# Transponder_Proaut_V1.net
KiCad netlist of a schematic drawn in EAGLE
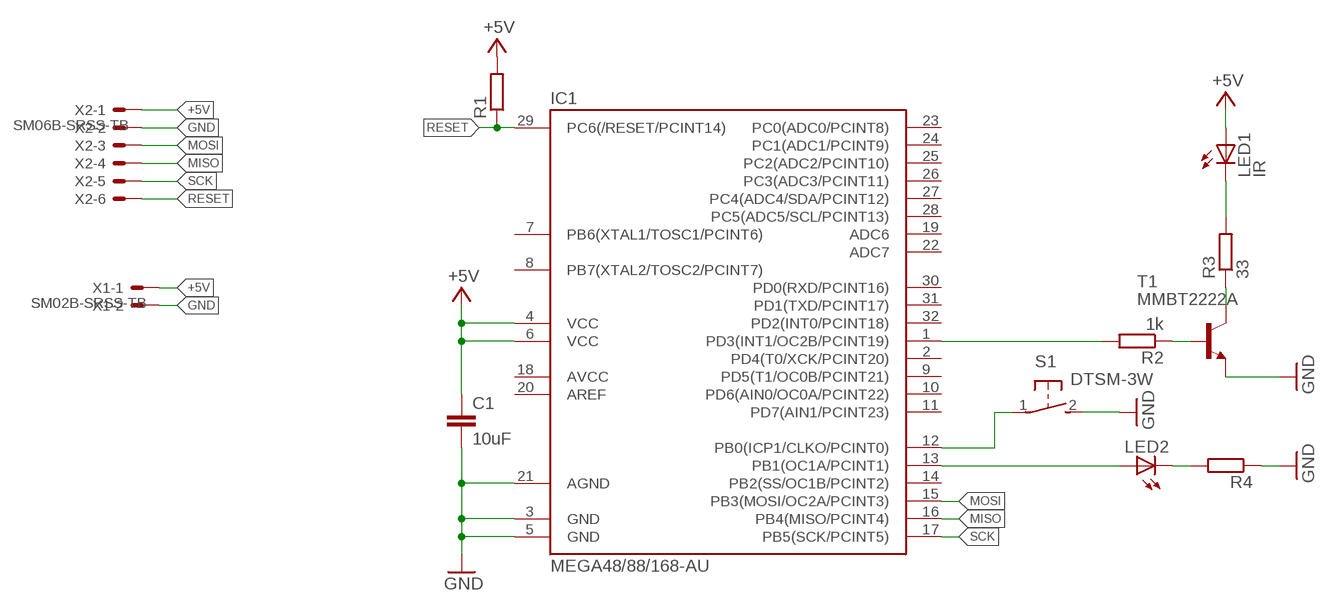
[diagram p0: schematic, sheet 1]

(export (version "E")
  (design (tool "Eeschema 10.0.6"))
  (components
    (comp (ref "C1")
      (value "10uF")
      (footprint "eagle-import:C0805")
      (libsource (lib "eagle-import") (part "C-EUC0805"))
    )
    (comp (ref "IC1")
      (value "MEGA48/88/168-AU")
      (footprint "eagle-import:TQFP32-08")
      (libsource (lib "eagle-import") (part "MEGA48/88/168-AU"))
    )
    (comp (ref "LED1")
      (value "IR")
      (footprint "eagle-import:LED5MM")
      (libsource (lib "eagle-import") (part "LED5MM"))
    )
    (comp (ref "LED2")
      (value "LEDSML1206")
      (footprint "eagle-import:SML1206")
      (libsource (lib "eagle-import") (part "LEDSML1206"))
    )
    (comp (ref "R1")
      (value "R-EU_R0805")
      (footprint "eagle-import:R0805@1")
      (libsource (lib "eagle-import") (part "R-EU_R0805"))
    )
    (comp (ref "R2")
      (value "1k")
      (footprint "eagle-import:R0805@1")
      (libsource (lib "eagle-import") (part "R-EU_R0805"))
    )
    (comp (ref "R3")
      (value "33")
      (footprint "eagle-import:R0805@1")
      (libsource (lib "eagle-import") (part "R-EU_R0805"))
    )
    (comp (ref "R4")
      (value "R-EU_R0805")
      (footprint "eagle-import:R0805@1")
      (libsource (lib "eagle-import") (part "R-EU_R0805"))
    )
    (comp (ref "S1")
      (value "DTSM-3W")
      (footprint "eagle-import:DTSM-3W")
      (libsource (lib "eagle-import") (part "DTSM-3W"))
    )
    (comp (ref "T1")
      (value "MMBT2222A")
      (footprint "eagle-import:SOT23-BEC")
      (libsource (lib "eagle-import") (part "-NPN-SOT23-BECMMBT2222ALT1"))
    )
    (comp (ref "X1")
      (value "SM02B-SRSS-TB")
      (footprint "eagle-import:SM02B-SRSS-TB")
      (libsource (lib "eagle-import") (part "?M02B-SRSS-TBS"))
    )
    (comp (ref "X2")
      (value "SM06B-SRSS-TB")
      (footprint "eagle-import:SM06B-SRSS-TB")
      (libsource (lib "eagle-import") (part "?M06B-SRSS-TBS"))
    )
  )
  (nets
    (net (code "1") (name "+5V") (class "Default")
      (node (ref "C1") (pin "1") (pinfunction "1_1") (pintype "passive"))
      (node (ref "IC1") (pin "4") (pinfunction "VCC_4") (pintype "power_in"))
      (node (ref "IC1") (pin "6") (pinfunction "VCC_6") (pintype "power_in"))
      (node (ref "LED1") (pin "A") (pinfunction "A_A") (pintype "passive"))
      (node (ref "R1") (pin "2") (pinfunction "2_2") (pintype "passive"))
      (node (ref "X1") (pin "1") (pinfunction "S_1") (pintype "passive"))
      (node (ref "X2") (pin "1") (pinfunction "S_1") (pintype "passive"))
    )
    (net (code "2") (name "GND") (class "Default")
      (node (ref "C1") (pin "2") (pinfunction "2_2") (pintype "passive"))
      (node (ref "IC1") (pin "21") (pinfunction "AGND_21") (pintype "power_in"))
      (node (ref "IC1") (pin "3") (pinfunction "GND_3") (pintype "power_in"))
      (node (ref "IC1") (pin "5") (pinfunction "GND_5") (pintype "power_in"))
      (node (ref "R4") (pin "1") (pinfunction "1_1") (pintype "passive"))
      (node (ref "S1") (pin "2") (pinfunction "2_2") (pintype "passive"))
      (node (ref "T1") (pin "E") (pinfunction "E_E") (pintype "passive"))
      (node (ref "X1") (pin "2") (pinfunction "S_2") (pintype "passive"))
      (node (ref "X2") (pin "2") (pinfunction "S_2") (pintype "passive"))
    )
    (net (code "3") (name "MISO") (class "Default")
      (node (ref "IC1") (pin "16") (pinfunction "PB4(MISO/PCINT4)_16") (pintype "bidirectional"))
      (node (ref "X2") (pin "4") (pinfunction "S_4") (pintype "passive"))
    )
    (net (code "4") (name "MOSI") (class "Default")
      (node (ref "IC1") (pin "15") (pinfunction "PB3(MOSI/OC2A/PCINT3)_15") (pintype "bidirectional"))
      (node (ref "X2") (pin "3") (pinfunction "S_3") (pintype "passive"))
    )
    (net (code "5") (name "Net-(IC1-PB0(ICP1{slash}CLKO{slash}PCINT0))") (class "Default")
      (node (ref "IC1") (pin "12") (pinfunction "PB0(ICP1/CLKO/PCINT0)_12") (pintype "bidirectional"))
      (node (ref "S1") (pin "1") (pinfunction "1_1") (pintype "passive"))
    )
    (net (code "6") (name "Net-(IC1-PB1(OC1A{slash}PCINT1))") (class "Default")
      (node (ref "IC1") (pin "13") (pinfunction "PB1(OC1A/PCINT1)_13") (pintype "bidirectional"))
      (node (ref "LED2") (pin "A") (pinfunction "A_A") (pintype "passive"))
    )
    (net (code "7") (name "Net-(IC1-PD3(INT1{slash}OC2B{slash}PCINT19))") (class "Default")
      (node (ref "IC1") (pin "1") (pinfunction "PD3(INT1/OC2B/PCINT19)_1") (pintype "bidirectional"))
      (node (ref "R2") (pin "2") (pinfunction "2_2") (pintype "passive"))
    )
    (net (code "8") (name "Net-(LED1-C)") (class "Default")
      (node (ref "LED1") (pin "K") (pinfunction "C_K") (pintype "passive"))
      (node (ref "R3") (pin "2") (pinfunction "2_2") (pintype "passive"))
    )
    (net (code "9") (name "Net-(LED2-PadC)") (class "Default")
      (node (ref "LED2") (pin "C") (pinfunction "C_C") (pintype "passive"))
      (node (ref "R4") (pin "2") (pinfunction "2_2") (pintype "passive"))
    )
    (net (code "10") (name "Net-(R2-Pad1)") (class "Default")
      (node (ref "R2") (pin "1") (pinfunction "1_1") (pintype "passive"))
      (node (ref "T1") (pin "B") (pinfunction "B_B") (pintype "passive"))
    )
    (net (code "11") (name "Net-(R3-Pad1)") (class "Default")
      (node (ref "R3") (pin "1") (pinfunction "1_1") (pintype "passive"))
      (node (ref "T1") (pin "C") (pinfunction "C_C") (pintype "passive"))
    )
    (net (code "12") (name "RESET") (class "Default")
      (node (ref "IC1") (pin "29") (pinfunction "PC6(/RESET/PCINT14)_29") (pintype "bidirectional"))
      (node (ref "R1") (pin "1") (pinfunction "1_1") (pintype "passive"))
      (node (ref "X2") (pin "6") (pinfunction "S_6") (pintype "passive"))
    )
    (net (code "13") (name "SCK") (class "Default")
      (node (ref "IC1") (pin "17") (pinfunction "PB5(SCK/PCINT5)_17") (pintype "bidirectional"))
      (node (ref "X2") (pin "5") (pinfunction "S_5") (pintype "passive"))
    )
    (net (code "14") (name "unconnected-(IC1-ADC6-Pad19)") (class "Default")
      (node (ref "IC1") (pin "19") (pinfunction "ADC6_19") (pintype "passive"))
    )
    (net (code "15") (name "unconnected-(IC1-ADC7-Pad22)") (class "Default")
      (node (ref "IC1") (pin "22") (pinfunction "ADC7_22") (pintype "passive"))
    )
    (net (code "16") (name "unconnected-(IC1-AREF-Pad20)") (class "Default")
      (node (ref "IC1") (pin "20") (pinfunction "AREF_20") (pintype "passive"))
    )
    (net (code "17") (name "unconnected-(IC1-AVCC-Pad18)") (class "Default")
      (node (ref "IC1") (pin "18") (pinfunction "AVCC_18") (pintype "passive"))
    )
    (net (code "18") (name "unconnected-(IC1-PB2(SS{slash}OC1B{slash}PCINT2)-Pad14)") (class "Default")
      (node (ref "IC1") (pin "14") (pinfunction "PB2(SS/OC1B/PCINT2)_14") (pintype "bidirectional"))
    )
    (net (code "19") (name "unconnected-(IC1-PB6(XTAL1{slash}TOSC1{slash}PCINT6)-Pad7)") (class "Default")
      (node (ref "IC1") (pin "7") (pinfunction "PB6(XTAL1/TOSC1/PCINT6)_7") (pintype "bidirectional"))
    )
    (net (code "20") (name "unconnected-(IC1-PB7(XTAL2{slash}TOSC2{slash}PCINT7)-Pad8)") (class "Default")
      (node (ref "IC1") (pin "8") (pinfunction "PB7(XTAL2/TOSC2/PCINT7)_8") (pintype "bidirectional"))
    )
    (net (code "21") (name "unconnected-(IC1-PC0(ADC0{slash}PCINT8)-Pad23)") (class "Default")
      (node (ref "IC1") (pin "23") (pinfunction "PC0(ADC0/PCINT8)_23") (pintype "bidirectional"))
    )
    (net (code "22") (name "unconnected-(IC1-PC1(ADC1{slash}PCINT9)-Pad24)") (class "Default")
      (node (ref "IC1") (pin "24") (pinfunction "PC1(ADC1/PCINT9)_24") (pintype "bidirectional"))
    )
    (net (code "23") (name "unconnected-(IC1-PC2(ADC2{slash}PCINT10)-Pad25)") (class "Default")
      (node (ref "IC1") (pin "25") (pinfunction "PC2(ADC2/PCINT10)_25") (pintype "bidirectional"))
    )
    (net (code "24") (name "unconnected-(IC1-PC3(ADC3{slash}PCINT11)-Pad26)") (class "Default")
      (node (ref "IC1") (pin "26") (pinfunction "PC3(ADC3/PCINT11)_26") (pintype "bidirectional"))
    )
    (net (code "25") (name "unconnected-(IC1-PC4(ADC4{slash}SDA{slash}PCINT12)-Pad27)") (class "Default")
      (node (ref "IC1") (pin "27") (pinfunction "PC4(ADC4/SDA/PCINT12)_27") (pintype "bidirectional"))
    )
    (net (code "26") (name "unconnected-(IC1-PC5(ADC5{slash}SCL{slash}PCINT13)-Pad28)") (class "Default")
      (node (ref "IC1") (pin "28") (pinfunction "PC5(ADC5/SCL/PCINT13)_28") (pintype "bidirectional"))
    )
    (net (code "27") (name "unconnected-(IC1-PD0(RXD{slash}PCINT16)-Pad30)") (class "Default")
      (node (ref "IC1") (pin "30") (pinfunction "PD0(RXD/PCINT16)_30") (pintype "bidirectional"))
    )
    (net (code "28") (name "unconnected-(IC1-PD1(TXD{slash}PCINT17)-Pad31)") (class "Default")
      (node (ref "IC1") (pin "31") (pinfunction "PD1(TXD/PCINT17)_31") (pintype "bidirectional"))
    )
    (net (code "29") (name "unconnected-(IC1-PD2(INT0{slash}PCINT18)-Pad32)") (class "Default")
      (node (ref "IC1") (pin "32") (pinfunction "PD2(INT0/PCINT18)_32") (pintype "bidirectional"))
    )
    (net (code "30") (name "unconnected-(IC1-PD4(T0{slash}XCK{slash}PCINT20)-Pad2)") (class "Default")
      (node (ref "IC1") (pin "2") (pinfunction "PD4(T0/XCK/PCINT20)_2") (pintype "bidirectional"))
    )
    (net (code "31") (name "unconnected-(IC1-PD5(T1{slash}OC0B{slash}PCINT21)-Pad9)") (class "Default")
      (node (ref "IC1") (pin "9") (pinfunction "PD5(T1/OC0B/PCINT21)_9") (pintype "bidirectional"))
    )
    (net (code "32") (name "unconnected-(IC1-PD6(AIN0{slash}OC0A{slash}PCINT22)-Pad10)") (class "Default")
      (node (ref "IC1") (pin "10") (pinfunction "PD6(AIN0/OC0A/PCINT22)_10") (pintype "bidirectional"))
    )
    (net (code "33") (name "unconnected-(IC1-PD7(AIN1{slash}PCINT23)-Pad11)") (class "Default")
      (node (ref "IC1") (pin "11") (pinfunction "PD7(AIN1/PCINT23)_11") (pintype "bidirectional"))
    )
  )
)
